# 7_SEGMENT_SCHEMATIC.net
KiCad netlist of a schematic drawn in EasyEDA
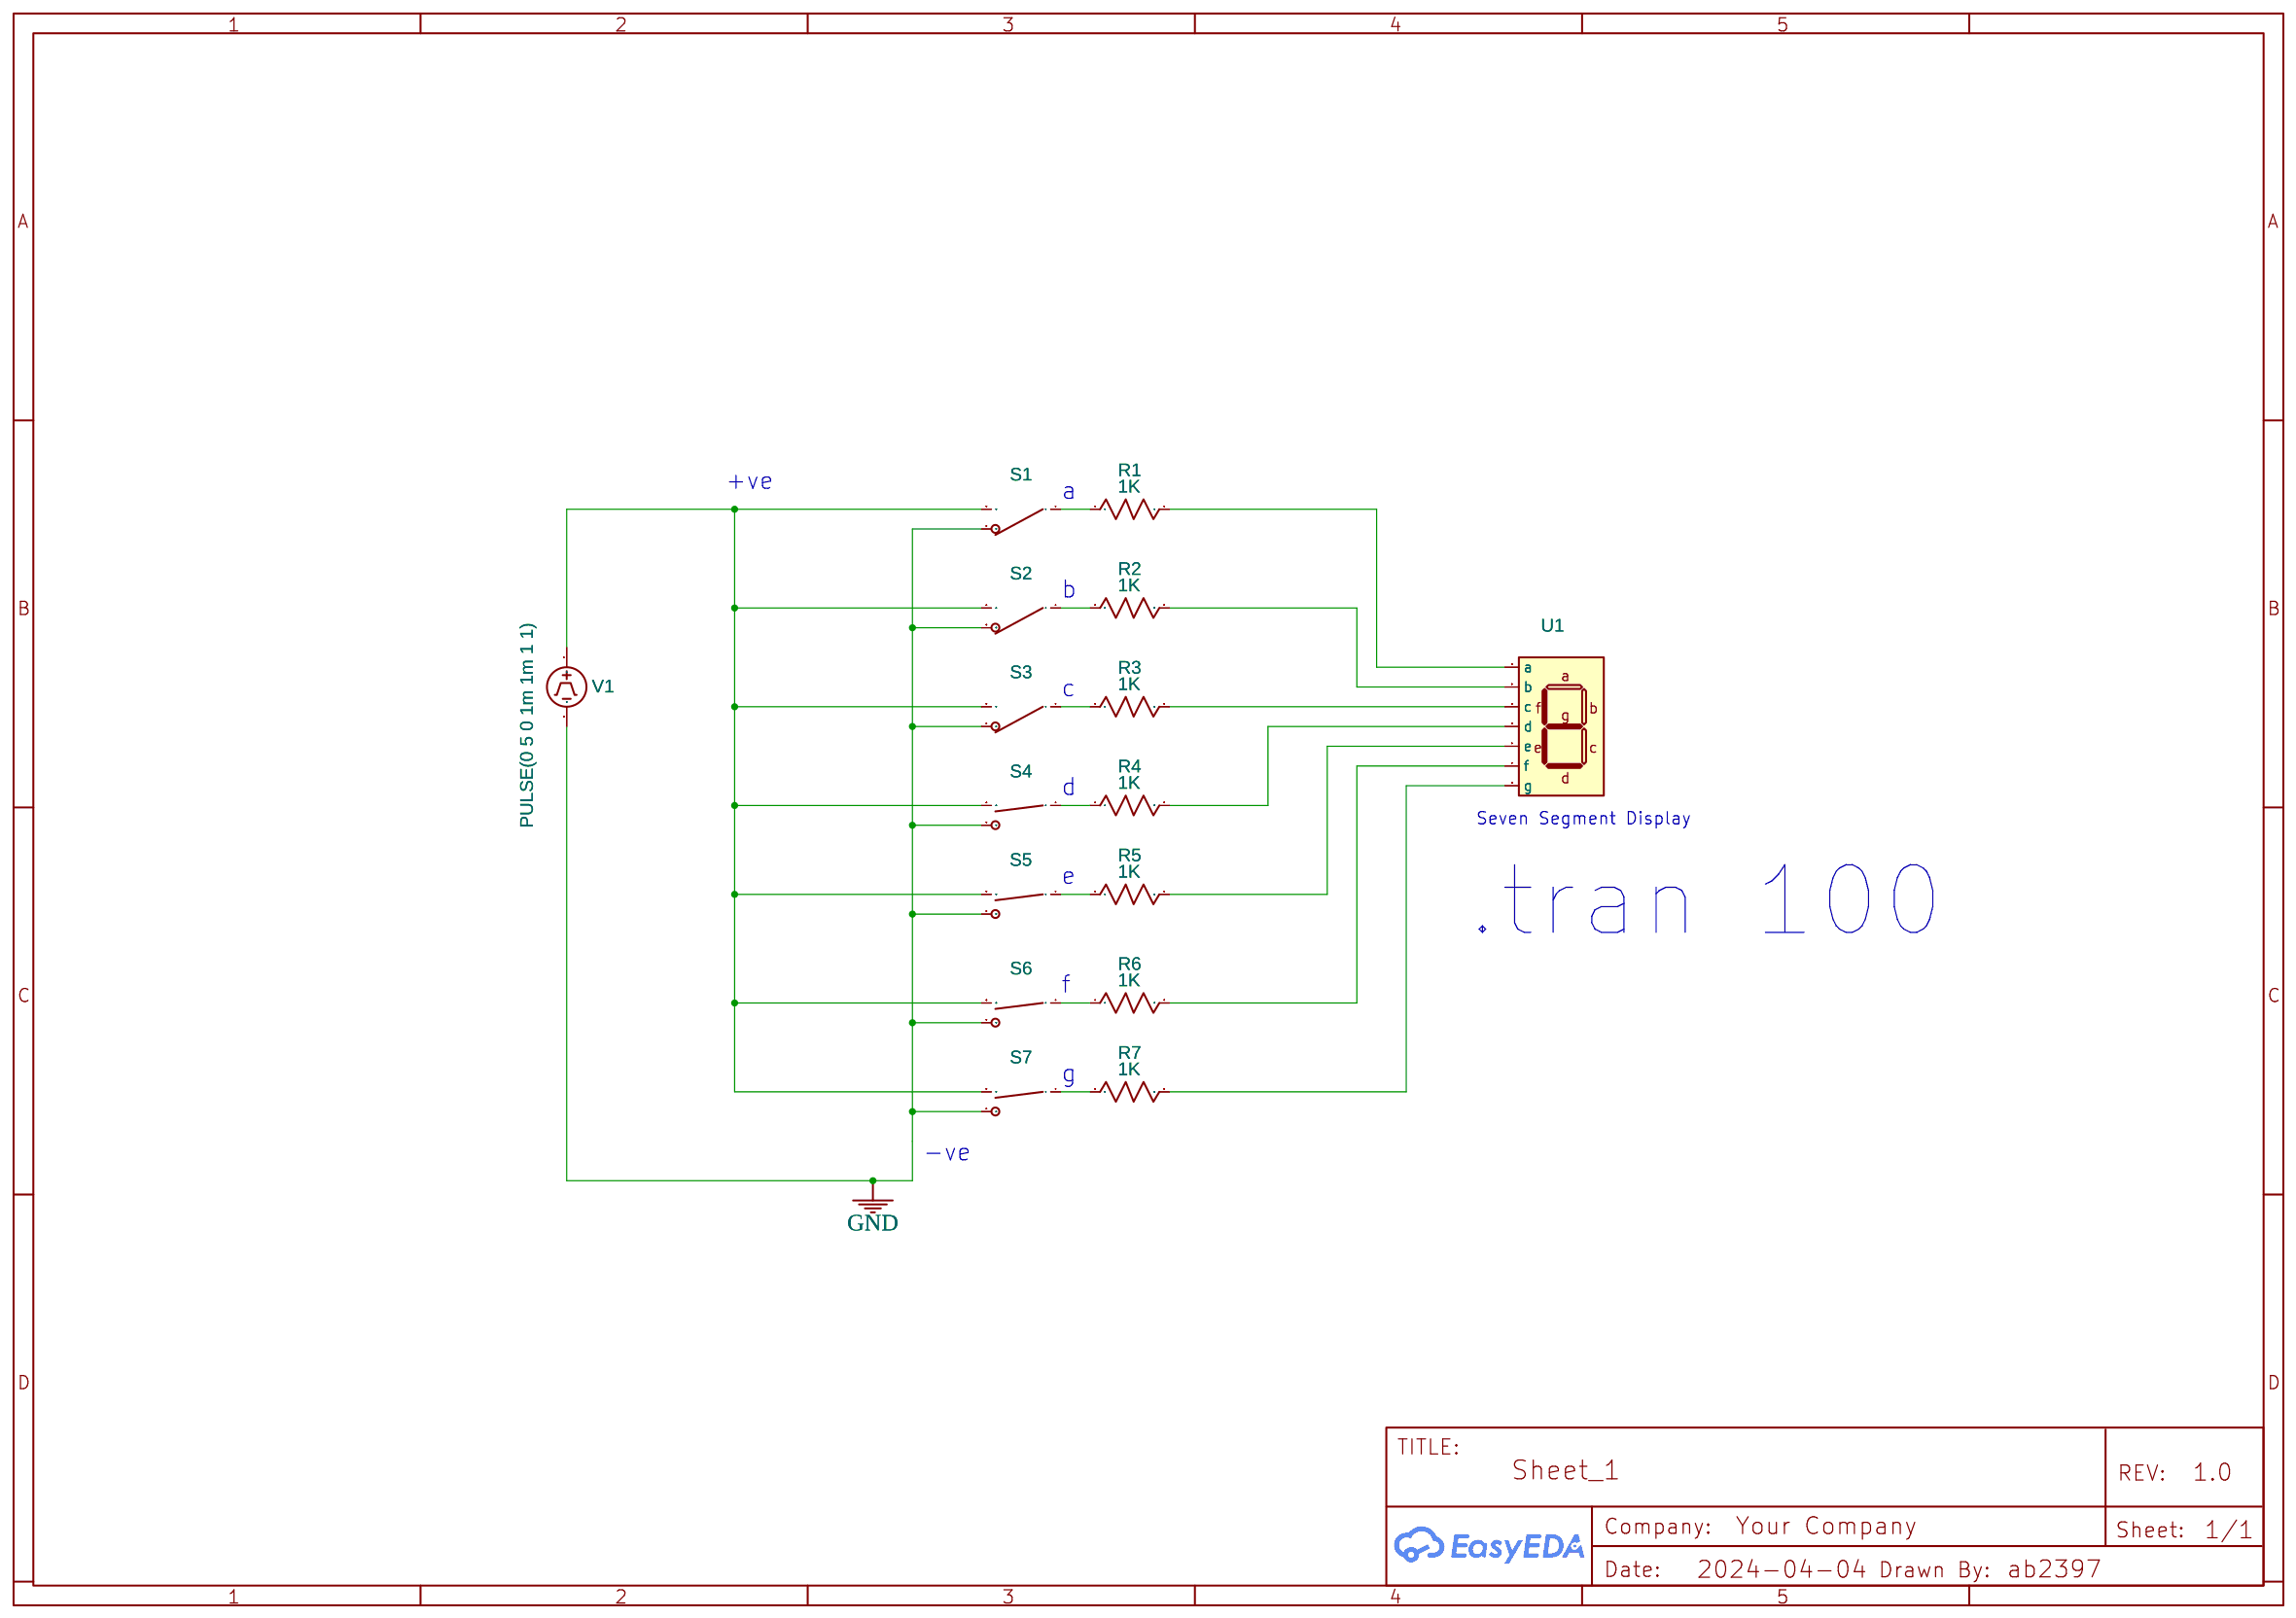
[diagram p0: schematic sheet]

(export (version "E")
  (design (tool "Eeschema 10.0.6"))
  (components
    (comp (ref "R1") (value "1K") (libsource (lib "") (part "Resistor_US")))
    (comp (ref "R2") (value "1K") (libsource (lib "") (part "Resistor_US")))
    (comp (ref "R3") (value "1K") (libsource (lib "") (part "Resistor_US")))
    (comp (ref "R4") (value "1K") (libsource (lib "") (part "Resistor_US")))
    (comp (ref "R5") (value "1K") (libsource (lib "") (part "Resistor_US")))
    (comp (ref "R6") (value "1K") (libsource (lib "") (part "Resistor_US")))
    (comp (ref "R7") (value "1K") (libsource (lib "") (part "Resistor_US")))
    (comp (ref "S1") (value "SPDT_Open") (libsource (lib "") (part "SPDT_1")))
    (comp (ref "S2") (value "SPDT_Open") (libsource (lib "") (part "SPDT_1")))
    (comp (ref "S3") (value "SPDT_Open") (libsource (lib "") (part "SPDT_1")))
    (comp (ref "S4") (value "SPDT_Open") (libsource (lib "") (part "SPDT")))
    (comp (ref "S5") (value "SPDT_Open") (libsource (lib "") (part "SPDT")))
    (comp (ref "S6") (value "SPDT_Open") (libsource (lib "") (part "SPDT")))
    (comp (ref "S7") (value "SPDT_Open") (libsource (lib "") (part "SPDT")))
    (comp (ref "U1") (value "Seven_Segment") (libsource (lib "") (part "SEVENSEGMENT")))
    (comp (ref "V1") (value "PULSE(0 5 0 1m 1m 1 1)") (libsource (lib "") (part "VPULSE")))
  )
  (nets
    (net (code "1") (name "GND") (class "Default")
      (node (ref "S1") (pin "2") (pinfunction "2_2") (pintype "unspecified"))
      (node (ref "S2") (pin "2") (pinfunction "2_2") (pintype "unspecified"))
      (node (ref "S3") (pin "2") (pinfunction "2_2") (pintype "unspecified"))
      (node (ref "S4") (pin "2") (pinfunction "2_2") (pintype "unspecified"))
      (node (ref "S5") (pin "2") (pinfunction "2_2") (pintype "unspecified"))
      (node (ref "S6") (pin "2") (pinfunction "2_2") (pintype "unspecified"))
      (node (ref "S7") (pin "2") (pinfunction "2_2") (pintype "unspecified"))
      (node (ref "V1") (pin "2") (pinfunction "2_2") (pintype "unspecified"))
    )
    (net (code "2") (name "Net-(R1-Pad1)") (class "Default")
      (node (ref "R1") (pin "1") (pinfunction "1_1") (pintype "unspecified"))
      (node (ref "S1") (pin "1") (pinfunction "1_1") (pintype "unspecified"))
    )
    (net (code "3") (name "Net-(R1-Pad2)") (class "Default")
      (node (ref "R1") (pin "2") (pinfunction "2_2") (pintype "unspecified"))
      (node (ref "U1") (pin "a") (pinfunction "a_a") (pintype "unspecified"))
    )
    (net (code "4") (name "Net-(R2-Pad1)") (class "Default")
      (node (ref "R2") (pin "1") (pinfunction "1_1") (pintype "unspecified"))
      (node (ref "S2") (pin "1") (pinfunction "1_1") (pintype "unspecified"))
    )
    (net (code "5") (name "Net-(R2-Pad2)") (class "Default")
      (node (ref "R2") (pin "2") (pinfunction "2_2") (pintype "unspecified"))
      (node (ref "U1") (pin "b") (pinfunction "b_b") (pintype "unspecified"))
    )
    (net (code "6") (name "Net-(R3-Pad1)") (class "Default")
      (node (ref "R3") (pin "1") (pinfunction "1_1") (pintype "unspecified"))
      (node (ref "S3") (pin "1") (pinfunction "1_1") (pintype "unspecified"))
    )
    (net (code "7") (name "Net-(R3-Pad2)") (class "Default")
      (node (ref "R3") (pin "2") (pinfunction "2_2") (pintype "unspecified"))
      (node (ref "U1") (pin "c") (pinfunction "c_c") (pintype "unspecified"))
    )
    (net (code "8") (name "Net-(R4-Pad1)") (class "Default")
      (node (ref "R4") (pin "1") (pinfunction "1_1") (pintype "unspecified"))
      (node (ref "S4") (pin "1") (pinfunction "1_1") (pintype "unspecified"))
    )
    (net (code "9") (name "Net-(R4-Pad2)") (class "Default")
      (node (ref "R4") (pin "2") (pinfunction "2_2") (pintype "unspecified"))
      (node (ref "U1") (pin "d") (pinfunction "d_d") (pintype "unspecified"))
    )
    (net (code "10") (name "Net-(R5-Pad1)") (class "Default")
      (node (ref "R5") (pin "1") (pinfunction "1_1") (pintype "unspecified"))
      (node (ref "S5") (pin "1") (pinfunction "1_1") (pintype "unspecified"))
    )
    (net (code "11") (name "Net-(R5-Pad2)") (class "Default")
      (node (ref "R5") (pin "2") (pinfunction "2_2") (pintype "unspecified"))
      (node (ref "U1") (pin "e") (pinfunction "e_e") (pintype "unspecified"))
    )
    (net (code "12") (name "Net-(R6-Pad1)") (class "Default")
      (node (ref "R6") (pin "1") (pinfunction "1_1") (pintype "unspecified"))
      (node (ref "S6") (pin "1") (pinfunction "1_1") (pintype "unspecified"))
    )
    (net (code "13") (name "Net-(R6-Pad2)") (class "Default")
      (node (ref "R6") (pin "2") (pinfunction "2_2") (pintype "unspecified"))
      (node (ref "U1") (pin "f") (pinfunction "f_f") (pintype "unspecified"))
    )
    (net (code "14") (name "Net-(R7-Pad1)") (class "Default")
      (node (ref "R7") (pin "1") (pinfunction "1_1") (pintype "unspecified"))
      (node (ref "S7") (pin "1") (pinfunction "1_1") (pintype "unspecified"))
    )
    (net (code "15") (name "Net-(R7-Pad2)") (class "Default")
      (node (ref "R7") (pin "2") (pinfunction "2_2") (pintype "unspecified"))
      (node (ref "U1") (pin "g") (pinfunction "g_g") (pintype "unspecified"))
    )
    (net (code "16") (name "Net-(S1-Pad3)") (class "Default")
      (node (ref "S1") (pin "3") (pinfunction "3_3") (pintype "unspecified"))
      (node (ref "S2") (pin "3") (pinfunction "3_3") (pintype "unspecified"))
      (node (ref "S3") (pin "3") (pinfunction "3_3") (pintype "unspecified"))
      (node (ref "S4") (pin "3") (pinfunction "3_3") (pintype "unspecified"))
      (node (ref "S5") (pin "3") (pinfunction "3_3") (pintype "unspecified"))
      (node (ref "S6") (pin "3") (pinfunction "3_3") (pintype "unspecified"))
      (node (ref "S7") (pin "3") (pinfunction "3_3") (pintype "unspecified"))
      (node (ref "V1") (pin "1") (pinfunction "1_1") (pintype "unspecified"))
    )
  )
)
